# Dent_Sheet_ESP.net
KiCad netlist of a schematic drawn in Altium Designer
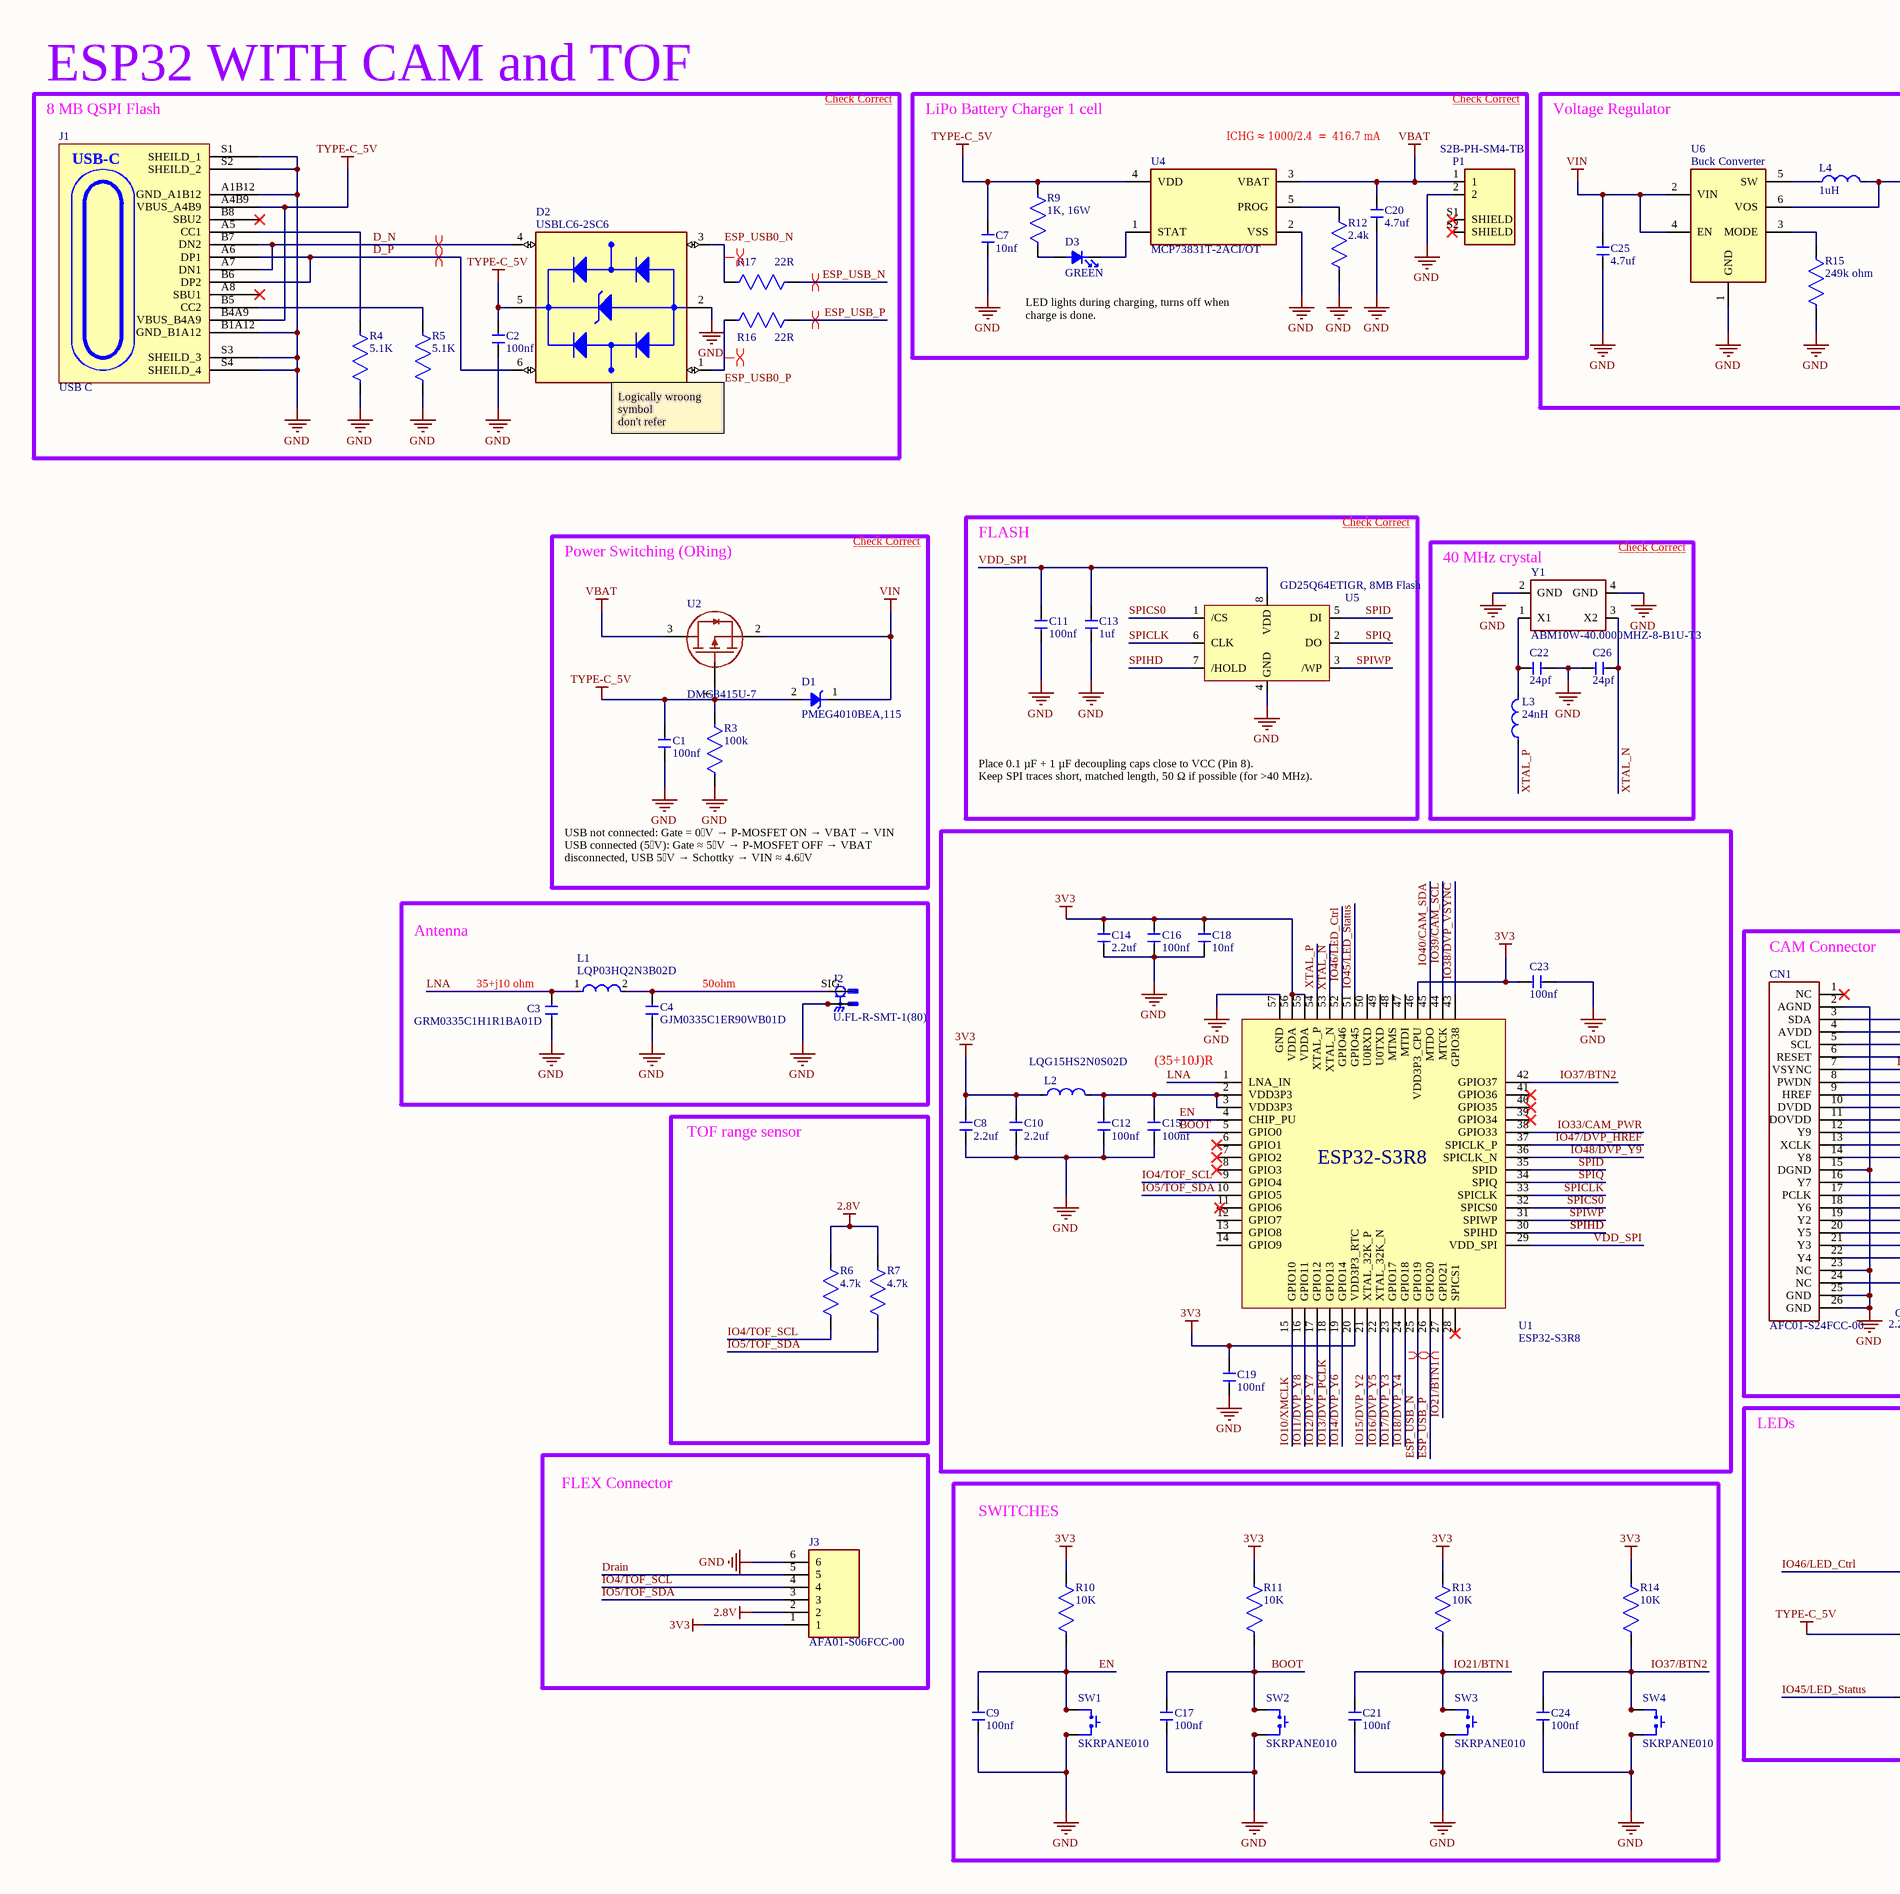
[diagram p0: Dent_Sheet_ESP.SchDoc, left]
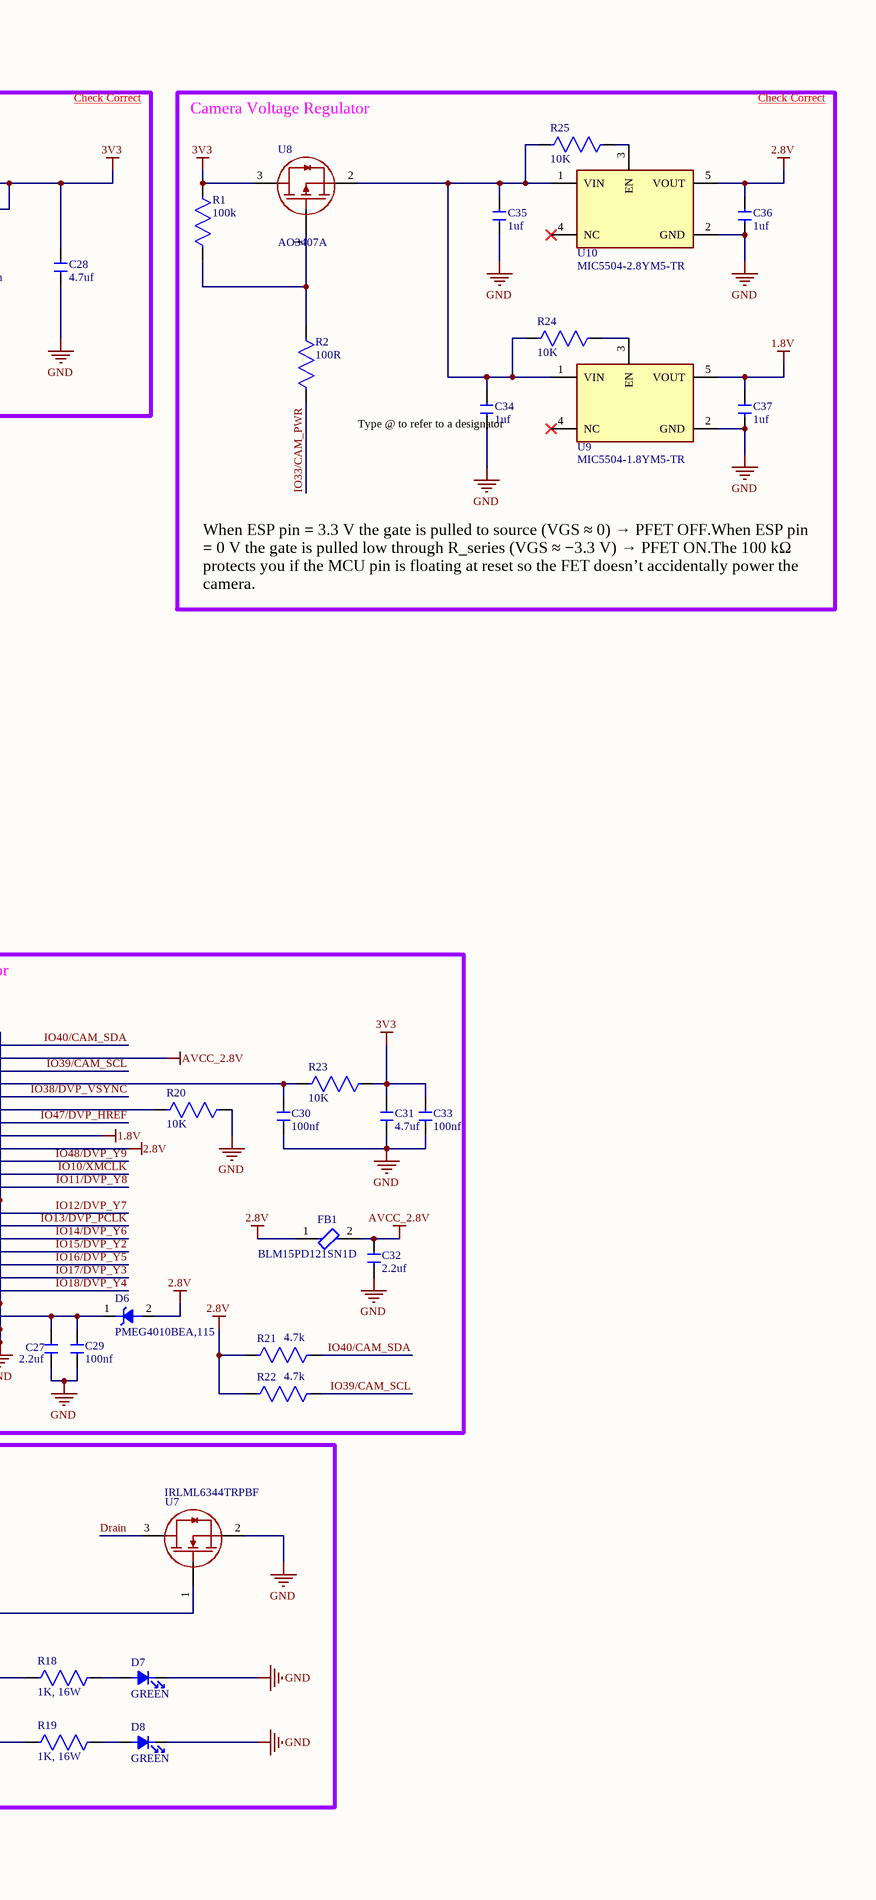
[diagram p1: Dent_Sheet_ESP.SchDoc, right]

(export (version "E")
  (design (tool "Eeschema 10.0.6"))
  (components
    (comp (ref "C1")
      (value "100nf")
      (footprint "CAPC1005X55N")
      (description "CAP CER 100NF 10V X7R 0402")
      (fields
        (field (name "MANUFACTURER") "Samsung")
        (field (name "MANUFACTURER PART NUMBER") "CL05B104KP5VPNC")
      )
      (libsource (lib "Dent_Schlib") (part "100nf"))
    )
    (comp (ref "C2")
      (value "100nf")
      (footprint "CAPC1005X55N")
      (description "CAP CER 100NF 10V X7R 0402")
      (fields
        (field (name "MANUFACTURER") "Samsung")
        (field (name "MANUFACTURER PART NUMBER") "CL05B104KP5VPNC")
      )
      (libsource (lib "Dent_Schlib") (part "100nf"))
    )
    (comp (ref "C3")
      (value "GRM0335C1H1R1BA01D")
      (footprint "FP-GRM033-0_03-MFG")
      (description "Chip Multilayer Ceramic Capacitors for General Purpose, 0201, 1.1pF, C0G, 30ppm/°C, 0.1pF, 50V")
      (fields (field (name "LCSC PART NO.") "C384969"))
      (libsource (lib "Dent_Schlib") (part "CMP-2010-01082-2"))
    )
    (comp (ref "C4")
      (value "GJM0335C1ER90WB01D")
      (footprint "FP-GJM033-0_03-MFG")
      (description "Ceramic Capacitor 0.9pF ±0.05pF 25V C0G 0201 (0603 Metric)")
      (fields (field (name "LCSC PART NO.") "C471401"))
      (libsource (lib "Dent_Schlib") (part "CMP-2010-00924-2"))
    )
    (comp (ref "C7")
      (value "10nf")
      (footprint "CAPC1005X55N")
      (description "CAP CER 10000PF 50V X7R 0402")
      (fields
        (field (name "MANUFACTURER") "Samsung")
        (field (name "MANUFACTURER PART NUMBER") "CL05B103KB5NNNC")
      )
      (libsource (lib "Dent_Schlib") (part "10nf"))
    )
    (comp (ref "C8")
      (value "2.2uf")
      (footprint "CAPC1005X55N")
      (description "CAP CER 2.2UF 10V X5R 0402")
      (fields
        (field (name "MANUFACTURER") "Samsung")
        (field (name "MANUFACTURER PART NUMBER") "CL05A225KP5NSNC")
      )
      (libsource (lib "Dent_Schlib") (part "2.2uf"))
    )
    (comp (ref "C9")
      (value "100nf")
      (footprint "CAPC1005X55N")
      (description "CAP CER 100NF 10V X7R 0402")
      (fields
        (field (name "MANUFACTURER") "Samsung")
        (field (name "MANUFACTURER PART NUMBER") "CL05B104KP5VPNC")
      )
      (libsource (lib "Dent_Schlib") (part "100nf"))
    )
    (comp (ref "C10")
      (value "2.2uf")
      (footprint "CAPC1005X55N")
      (description "CAP CER 2.2UF 10V X5R 0402")
      (fields
        (field (name "MANUFACTURER") "Samsung")
        (field (name "MANUFACTURER PART NUMBER") "CL05A225KP5NSNC")
      )
      (libsource (lib "Dent_Schlib") (part "2.2uf"))
    )
    (comp (ref "C11")
      (value "100nf")
      (footprint "CAPC1005X55N")
      (description "CAP CER 100NF 10V X7R 0402")
      (fields
        (field (name "MANUFACTURER") "Samsung")
        (field (name "MANUFACTURER PART NUMBER") "CL05B104KP5VPNC")
      )
      (libsource (lib "Dent_Schlib") (part "100nf"))
    )
    (comp (ref "C12")
      (value "100nf")
      (footprint "CAPC1005X55N")
      (description "CAP CER 100NF 10V X7R 0402")
      (fields
        (field (name "MANUFACTURER") "Samsung")
        (field (name "MANUFACTURER PART NUMBER") "CL05B104KP5VPNC")
      )
      (libsource (lib "Dent_Schlib") (part "100nf"))
    )
    (comp (ref "C13")
      (value "1uf")
      (footprint "CAPC1005X55N")
      (description "CAP CER 1UF 25V X5R 0402")
      (fields
        (field (name "MANUFACTURER") "Samsung")
        (field (name "MANUFACTURER PART NUMBER") "CL05A105KA5NQNC")
      )
      (libsource (lib "Dent_Schlib") (part "1uf"))
    )
    (comp (ref "C14")
      (value "2.2uf")
      (footprint "CAPC1005X55N")
      (description "CAP CER 2.2UF 10V X5R 0402")
      (fields
        (field (name "MANUFACTURER") "Samsung")
        (field (name "MANUFACTURER PART NUMBER") "CL05A225KP5NSNC")
      )
      (libsource (lib "Dent_Schlib") (part "2.2uf"))
    )
    (comp (ref "C15")
      (value "100nf")
      (footprint "CAPC1005X55N")
      (description "CAP CER 100NF 10V X7R 0402")
      (fields
        (field (name "MANUFACTURER") "Samsung")
        (field (name "MANUFACTURER PART NUMBER") "CL05B104KP5VPNC")
      )
      (libsource (lib "Dent_Schlib") (part "100nf"))
    )
    (comp (ref "C16")
      (value "100nf")
      (footprint "CAPC1005X55N")
      (description "CAP CER 100NF 10V X7R 0402")
      (fields
        (field (name "MANUFACTURER") "Samsung")
        (field (name "MANUFACTURER PART NUMBER") "CL05B104KP5VPNC")
      )
      (libsource (lib "Dent_Schlib") (part "100nf"))
    )
    (comp (ref "C17")
      (value "100nf")
      (footprint "CAPC1005X55N")
      (description "CAP CER 100NF 10V X7R 0402")
      (fields
        (field (name "MANUFACTURER") "Samsung")
        (field (name "MANUFACTURER PART NUMBER") "CL05B104KP5VPNC")
      )
      (libsource (lib "Dent_Schlib") (part "100nf"))
    )
    (comp (ref "C18")
      (value "10nf")
      (footprint "CAPC1005X55N")
      (description "CAP CER 10000PF 50V X7R 0402")
      (fields
        (field (name "MANUFACTURER") "Samsung")
        (field (name "MANUFACTURER PART NUMBER") "CL05B103KB5NNNC")
      )
      (libsource (lib "Dent_Schlib") (part "10nf"))
    )
    (comp (ref "C19")
      (value "100nf")
      (footprint "CAPC1005X55N")
      (description "CAP CER 100NF 10V X7R 0402")
      (fields
        (field (name "MANUFACTURER") "Samsung")
        (field (name "MANUFACTURER PART NUMBER") "CL05B104KP5VPNC")
      )
      (libsource (lib "Dent_Schlib") (part "100nf"))
    )
    (comp (ref "C20")
      (value "4.7uf")
      (footprint "CAPC1005X55N")
      (description "CAP CER 4.7UF 10V X5R 0402")
      (fields
        (field (name "MANUFACTURER") "Samsung")
        (field (name "MANUFACTURER PART NUMBER") "CL05A475KP5ZRNC")
      )
      (libsource (lib "Dent_Schlib") (part "4.7uf"))
    )
    (comp (ref "C21")
      (value "100nf")
      (footprint "CAPC1005X55N")
      (description "CAP CER 100NF 10V X7R 0402")
      (fields
        (field (name "MANUFACTURER") "Samsung")
        (field (name "MANUFACTURER PART NUMBER") "CL05B104KP5VPNC")
      )
      (libsource (lib "Dent_Schlib") (part "100nf"))
    )
    (comp (ref "C22")
      (value "24pf")
      (footprint "CAPC1005X55N")
      (description "CAP CER 24PF 50V C0G/NPO 0402")
      (fields
        (field (name "MANUFACTURER") "Yageo")
        (field (name "MANUFACTURER PART NUMBER") "CC0402GRNPO9BN240")
      )
      (libsource (lib "Dent_Schlib") (part "24pf"))
    )
    (comp (ref "C23")
      (value "100nf")
      (footprint "CAPC1005X55N")
      (description "CAP CER 100NF 10V X7R 0402")
      (fields
        (field (name "MANUFACTURER") "Samsung")
        (field (name "MANUFACTURER PART NUMBER") "CL05B104KP5VPNC")
      )
      (libsource (lib "Dent_Schlib") (part "100nf"))
    )
    (comp (ref "C24")
      (value "100nf")
      (footprint "CAPC1005X55N")
      (description "CAP CER 100NF 10V X7R 0402")
      (fields
        (field (name "MANUFACTURER") "Samsung")
        (field (name "MANUFACTURER PART NUMBER") "CL05B104KP5VPNC")
      )
      (libsource (lib "Dent_Schlib") (part "100nf"))
    )
    (comp (ref "C25")
      (value "4.7uf")
      (footprint "CAPC1005X55N")
      (description "CAP CER 4.7UF 10V X5R 0402")
      (fields
        (field (name "MANUFACTURER") "Samsung")
        (field (name "MANUFACTURER PART NUMBER") "CL05A475KP5ZRNC")
      )
      (libsource (lib "Dent_Schlib") (part "4.7uf"))
    )
    (comp (ref "C26")
      (value "24pf")
      (footprint "CAPC1005X55N")
      (description "CAP CER 24PF 50V C0G/NPO 0402")
      (fields
        (field (name "MANUFACTURER") "Yageo")
        (field (name "MANUFACTURER PART NUMBER") "CC0402GRNPO9BN240")
      )
      (libsource (lib "Dent_Schlib") (part "24pf"))
    )
    (comp (ref "C27")
      (value "2.2uf")
      (footprint "CAPC1005X55N")
      (description "CAP CER 2.2UF 10V X5R 0402")
      (fields
        (field (name "MANUFACTURER") "Samsung")
        (field (name "MANUFACTURER PART NUMBER") "CL05A225KP5NSNC")
      )
      (libsource (lib "Dent_Schlib") (part "2.2uf"))
    )
    (comp (ref "C28")
      (value "4.7uf")
      (footprint "CAPC1005X55N")
      (description "CAP CER 4.7UF 10V X5R 0402")
      (fields
        (field (name "MANUFACTURER") "Samsung")
        (field (name "MANUFACTURER PART NUMBER") "CL05A475KP5ZRNC")
      )
      (libsource (lib "Dent_Schlib") (part "4.7uf"))
    )
    (comp (ref "C29")
      (value "100nf")
      (footprint "CAPC1005X55N")
      (description "CAP CER 100NF 10V X7R 0402")
      (fields
        (field (name "MANUFACTURER") "Samsung")
        (field (name "MANUFACTURER PART NUMBER") "CL05B104KP5VPNC")
      )
      (libsource (lib "Dent_Schlib") (part "100nf"))
    )
    (comp (ref "C30")
      (value "100nf")
      (footprint "CAPC1005X55N")
      (description "CAP CER 100NF 10V X7R 0402")
      (fields
        (field (name "MANUFACTURER") "Samsung")
        (field (name "MANUFACTURER PART NUMBER") "CL05B104KP5VPNC")
      )
      (libsource (lib "Dent_Schlib") (part "100nf"))
    )
    (comp (ref "C31")
      (value "4.7uf")
      (footprint "CAPC1005X55N")
      (description "CAP CER 4.7UF 10V X5R 0402")
      (fields
        (field (name "MANUFACTURER") "Samsung")
        (field (name "MANUFACTURER PART NUMBER") "CL05A475KP5ZRNC")
      )
      (libsource (lib "Dent_Schlib") (part "4.7uf"))
    )
    (comp (ref "C32")
      (value "2.2uf")
      (footprint "CAPC1005X55N")
      (description "CAP CER 2.2UF 10V X5R 0402")
      (fields
        (field (name "MANUFACTURER") "Samsung")
        (field (name "MANUFACTURER PART NUMBER") "CL05A225KP5NSNC")
      )
      (libsource (lib "Dent_Schlib") (part "2.2uf"))
    )
    (comp (ref "C33")
      (value "100nf")
      (footprint "CAPC1005X55N")
      (description "CAP CER 100NF 10V X7R 0402")
      (fields
        (field (name "MANUFACTURER") "Samsung")
        (field (name "MANUFACTURER PART NUMBER") "CL05B104KP5VPNC")
      )
      (libsource (lib "Dent_Schlib") (part "100nf"))
    )
    (comp (ref "C34")
      (value "1uf")
      (footprint "CAPC1005X55N")
      (description "CAP CER 1UF 25V X5R 0402")
      (fields
        (field (name "MANUFACTURER") "Samsung")
        (field (name "MANUFACTURER PART NUMBER") "CL05A105KA5NQNC")
      )
      (libsource (lib "Dent_Schlib") (part "1uf"))
    )
    (comp (ref "C35")
      (value "1uf")
      (footprint "CAPC1005X55N")
      (description "CAP CER 1UF 25V X5R 0402")
      (fields
        (field (name "MANUFACTURER") "Samsung")
        (field (name "MANUFACTURER PART NUMBER") "CL05A105KA5NQNC")
      )
      (libsource (lib "Dent_Schlib") (part "1uf"))
    )
    (comp (ref "C36")
      (value "1uf")
      (footprint "CAPC1005X55N")
      (description "CAP CER 1UF 25V X5R 0402")
      (fields
        (field (name "MANUFACTURER") "Samsung")
        (field (name "MANUFACTURER PART NUMBER") "CL05A105KA5NQNC")
      )
      (libsource (lib "Dent_Schlib") (part "1uf"))
    )
    (comp (ref "C37")
      (value "1uf")
      (footprint "CAPC1005X55N")
      (description "CAP CER 1UF 25V X5R 0402")
      (fields
        (field (name "MANUFACTURER") "Samsung")
        (field (name "MANUFACTURER PART NUMBER") "CL05A105KA5NQNC")
      )
      (libsource (lib "Dent_Schlib") (part "1uf"))
    )
    (comp (ref "CN1")
      (value "AFC01-S24FCC-00")
      (footprint "FH52-24S-0.5SH")
      (description "SMD,P=0.5mm,Surface Mount,Right Angle")
      (fields (field (name "MANUFACTURER") "Hirose") (field (name "LCSC PART NO.") "C262276"))
      (libsource (lib "Dent_Schlib") (part "AFC01-S24FCC-00"))
    )
    (comp (ref "D1")
      (value "PMEG4010BEA,115")
      (footprint "SOD2512X110N")
      (description "DIODE SCHOTTKY 40V 1A SOD323")
      (fields (field (name "MANUFACTURER") "Nexperia") (field (name "LCSC PART NO.") "C36975"))
      (libsource (lib "Dent_Schlib") (part "PMEG4010BEA,115"))
    )
    (comp (ref "D2")
      (value "USBLC6-2SC6")
      (footprint "SOT95P280X145-6N")
      (description "17V Clamp 5A (8/20µs) Ipp Tvs Diode Surface Mount SOT-23-6")
      (fields (field (name "MANUFACTURER") "STMicroelectronics") (field (name "LCSC PART NO.") "C7519"))
      (libsource (lib "Dent_Schlib") (part "USBLC6-2SC6"))
    )
    (comp (ref "D3")
      (value "GREEN")
      (footprint "LEDC1005X35N")
      (description "LED YLW-GRN 0402 SMD")
      (fields
        (field (name "MANUFACTURER") "Vishay")
        (field (name "MANUFACTURER PART NUMBER") "VLMG1500-GS08")
      )
      (libsource (lib "Dent_Schlib") (part "VLMG1500-GS08"))
    )
    (comp (ref "D6")
      (value "PMEG4010BEA,115")
      (footprint "SOD2512X110N")
      (description "DIODE SCHOTTKY 40V 1A SOD323")
      (fields (field (name "MANUFACTURER") "Nexperia") (field (name "LCSC PART NO.") "C36975"))
      (libsource (lib "Dent_Schlib") (part "PMEG4010BEA,115"))
    )
    (comp (ref "D7")
      (value "GREEN")
      (footprint "LEDC1005X35N")
      (description "LED YLW-GRN 0402 SMD")
      (fields
        (field (name "MANUFACTURER") "Vishay")
        (field (name "MANUFACTURER PART NUMBER") "VLMG1500-GS08")
      )
      (libsource (lib "Dent_Schlib") (part "VLMG1500-GS08"))
    )
    (comp (ref "D8")
      (value "GREEN")
      (footprint "LEDC1005X35N")
      (description "LED YLW-GRN 0402 SMD")
      (fields
        (field (name "MANUFACTURER") "Vishay")
        (field (name "MANUFACTURER PART NUMBER") "VLMG1500-GS08")
      )
      (libsource (lib "Dent_Schlib") (part "VLMG1500-GS08"))
    )
    (comp (ref "FB1")
      (value "BLM15PD121SN1D")
      (footprint "FP-BLM15-0_05-IPC_B")
      (description "Chip Ferrite Bead, 0402, 120Ω @ 100MHz, 0.09Ω, 25%, 1.3A")
      (fields (field (name "TOLERANCE") "25%") (field (name "LCSC PART NO.") "C76891"))
      (libsource (lib "Dent_Schlib") (part "BLM15PD121SN1D"))
    )
    (comp (ref "J1")
      (value "USB C")
      (footprint "FP-2171790001-MFG")
      (description "USB Connector, USB Type C, USB 2.0, Receptacle, 16 Ways, Surface Mount, Through Hole Mount")
      (fields (field (name "MANUFACTURER") "Molex") (field (name "MANUFACTURER PART NUMBER") "217179-0001"))
      (libsource (lib "Dent_Schlib") (part "217179-0001"))
    )
    (comp (ref "J2")
      (value "U.FL-R-SMT-1(80)")
      (footprint "HIROSE_U.FL-R-SMT-1(80)")
      (description "U.FL (UMCC) Connector Receptacle, Male Pin 50 Ohms Surface Mount Solder")
      (fields (field (name "LCSC PART NO.") "C88374"))
      (libsource (lib "Dent_Schlib") (part "U.FL-R-SMT-1(80)"))
    )
    (comp (ref "J3")
      (value "AFA01-S06FCC-00")
      (footprint "JUSHUO_AFA01-S06FCC-00")
      (description "Pitch 1.00mm FPC Connector SMT Type")
      (fields (field (name "MF") "Shenzhen Jushuo Electronics Co") (field (name "LCSC PART NO.") "C262262"))
      (libsource (lib "Dent_Schlib") (part "AFA01-S06FCC-00"))
    )
    (comp (ref "L1")
      (value "LQP03HQ2N3B02D")
      (footprint "FP-LQP02HV_02-MFG")
      (description "Film type RF Inductor 2.3nH ±0.1nH 600mA 0.12Ω 0201 (0603)")
      (fields (field (name "LCSC PART NO.") "C2975186"))
      (libsource (lib "Dent_Schlib") (part "CMP-06042-004543-1"))
    )
    (comp (ref "L2")
      (value "LQG15HS2N0S02D")
      (footprint "INDC1005X55N")
      (description "Inductor RF Chip Multi-Layer 2nH 0.3nH 100MHz 8Q-Factor Air 300mA 100mOhm DCR 0402 Paper T/R")
      (fields (field (name "MANUFACTURER") "Murata") (field (name "TOLERANCE") "15%"))
      (libsource (lib "Dent_Schlib") (part "LQG15HS2N0S02D"))
    )
    (comp (ref "L3")
      (value "24nH")
      (footprint "INDC1005X60N")
      (description "FIXED IND 24NH 280MA 0.52OHM SMD")
      (fields
        (field (name "MANUFACTURER") "Murata")
        (field (name "MANUFACTURER PART NUMBER") "LQW15AN24NJ00D")
      )
      (libsource (lib "Dent_Schlib") (part "24nH"))
    )
    (comp (ref "L4")
      (value "1uH")
      (footprint "INDC2016X100N")
      (description "1 µH Shielded Drum Core, Wirewound Inductor 3.1 A 70mOhm Max 0806 (2016 Metric)")
      (fields
        (field (name "MANUFACTURER") "Murata")
        (field (name "MANUFACTURER PART NUMBER") "DFE201610P-1R0M=P2")
      )
      (libsource (lib "Dent_Schlib") (part "1uH"))
    )
    (comp (ref "P1")
      (value "S2B-PH-SM4-TB")
      (footprint "JST_S2B-PH-SM4-TB(LF)(SN)")
      (description "Header S2B-PH-SM4-TB, 2.00mm, 2-contacts, side entry, SMT, /1000/reel")
      (fields (field (name "MANUFACTURER") "JST") (field (name "LCSC PART NO.") "C295747"))
      (libsource (lib "Dent_Schlib") (part "S2B-PH-SM4-TB"))
    )
    (comp (ref "R1")
      (value "100k")
      (footprint "RESC1005X40N")
      (description "RES 100K OHM 1% 1/16W 0402")
      (fields
        (field (name "MANUFACTURER") "Yageo")
        (field (name "MANUFACTURER PART NUMBER") "RC0402FR-07100KL")
      )
      (libsource (lib "Dent_Schlib") (part "100k"))
    )
    (comp (ref "R2")
      (value "100R")
      (footprint "RESC1005X40N")
      (fields
        (field (name "MANUFACTURER") "Yageo")
        (field (name "MANUFACTURER PART NUMBER") "RC0402JR-07100KL")
        (field (name "TOLERANCE") "5%")
      )
      (libsource (lib "Dent_Schlib") (part "100R"))
    )
    (comp (ref "R3")
      (value "100k")
      (footprint "RESC1005X40N")
      (description "RES 100K OHM 1% 1/16W 0402")
      (fields
        (field (name "MANUFACTURER") "Yageo")
        (field (name "MANUFACTURER PART NUMBER") "RC0402FR-07100KL")
      )
      (libsource (lib "Dent_Schlib") (part "100k"))
    )
    (comp (ref "R4")
      (value "5.1K")
      (footprint "RESC1005X40N")
      (fields
        (field (name "MANUFACTURER") "Yageo")
        (field (name "MANUFACTURER PART NUMBER") "RC0402FR-075K1L")
        (field (name "TOLERANCE") "1%")
      )
      (libsource (lib "Dent_Schlib") (part "5.1K"))
    )
    (comp (ref "R5")
      (value "5.1K")
      (footprint "RESC1005X40N")
      (fields
        (field (name "MANUFACTURER") "Yageo")
        (field (name "MANUFACTURER PART NUMBER") "RC0402FR-075K1L")
        (field (name "TOLERANCE") "1%")
      )
      (libsource (lib "Dent_Schlib") (part "5.1K"))
    )
    (comp (ref "R6")
      (value "4.7k")
      (footprint "RESC1005X40N")
      (description "RES 4.7K OHM 1% 1/16W 0402")
      (fields
        (field (name "MANUFACTURER") "Yageo")
        (field (name "MANUFACTURER PART NUMBER") "RC0402FR-074K7L")
      )
      (libsource (lib "Dent_Schlib") (part "4.7k"))
    )
    (comp (ref "R7")
      (value "4.7k")
      (footprint "RESC1005X40N")
      (description "RES 4.7K OHM 1% 1/16W 0402")
      (fields
        (field (name "MANUFACTURER") "Yageo")
        (field (name "MANUFACTURER PART NUMBER") "RC0402FR-074K7L")
      )
      (libsource (lib "Dent_Schlib") (part "4.7k"))
    )
    (comp (ref "R9")
      (value "1K, 16W")
      (footprint "RESC1005X40N")
      (description "RES 1K OHM 1% 1/16W 0402")
      (fields
        (field (name "MANUFACTURER") "Yageo")
        (field (name "MANUFACTURER PART NUMBER") "RC0402FR-071KL")
      )
      (libsource (lib "Dent_Schlib") (part "1K, 16W"))
    )
    (comp (ref "R10")
      (value "10K")
      (footprint "RESC1005X40N")
      (description "Res Thick Film 0402 10K Ohm 5% 0.125W(1/8W) ±200ppm/C Pad SMD T/R")
      (fields
        (field (name "MANUFACTURER") "Yageo Group")
        (field (name "MANUFACTURER PART NUMBER") "RC0402JR-7W10KL")
      )
      (libsource (lib "Dent_Schlib") (part "10K"))
    )
    (comp (ref "R11")
      (value "10K")
      (footprint "RESC1005X40N")
      (description "Res Thick Film 0402 10K Ohm 5% 0.125W(1/8W) ±200ppm/C Pad SMD T/R")
      (fields
        (field (name "MANUFACTURER") "Yageo Group")
        (field (name "MANUFACTURER PART NUMBER") "RC0402JR-7W10KL")
      )
      (libsource (lib "Dent_Schlib") (part "10K"))
    )
    (comp (ref "R12")
      (value "2.4k")
      (footprint "RESC1005X40N")
      (description "RES SMD 2.4K OHM 1% 1/16W 0402")
      (fields
        (field (name "MANUFACTURER") "Samsung")
        (field (name "MANUFACTURER PART NUMBER") "RC1005F242CS")
      )
      (libsource (lib "Dent_Schlib") (part "2.4k"))
    )
    (comp (ref "R13")
      (value "10K")
      (footprint "RESC1005X40N")
      (description "Res Thick Film 0402 10K Ohm 5% 0.125W(1/8W) ±200ppm/C Pad SMD T/R")
      (fields
        (field (name "MANUFACTURER") "Yageo Group")
        (field (name "MANUFACTURER PART NUMBER") "RC0402JR-7W10KL")
      )
      (libsource (lib "Dent_Schlib") (part "10K"))
    )
    (comp (ref "R14")
      (value "10K")
      (footprint "RESC1005X40N")
      (description "Res Thick Film 0402 10K Ohm 5% 0.125W(1/8W) ±200ppm/C Pad SMD T/R")
      (fields
        (field (name "MANUFACTURER") "Yageo Group")
        (field (name "MANUFACTURER PART NUMBER") "RC0402JR-7W10KL")
      )
      (libsource (lib "Dent_Schlib") (part "10K"))
    )
    (comp (ref "R15")
      (value "249k ohm")
      (footprint "RESC1005X40N")
      (description "249 kOhms ±1% 0.063W, 1/16W Chip Resistor 0402 (1005 Metric) Moisture Resistant Thick Film")
      (fields
        (field (name "MANUFACTURER") "Yageo")
        (field (name "MANUFACTURER PART NUMBER") "RC0402FR-07249KL")
      )
      (libsource (lib "Dent_Schlib") (part "249k ohm"))
    )
    (comp (ref "R16")
      (value "22R")
      (footprint "RESC1005X40N")
      (description "RES 22 OHM 5% 1/8W 0402")
      (fields
        (field (name "MANUFACTURER") "Yageo Group")
        (field (name "MANUFACTURER PART NUMBER") "AC0402JR-7W22RL")
      )
      (libsource (lib "Dent_Schlib") (part "22R"))
    )
    (comp (ref "R17")
      (value "22R")
      (footprint "RESC1005X40N")
      (description "RES 22 OHM 5% 1/8W 0402")
      (fields
        (field (name "MANUFACTURER") "Yageo Group")
        (field (name "MANUFACTURER PART NUMBER") "AC0402JR-7W22RL")
      )
      (libsource (lib "Dent_Schlib") (part "22R"))
    )
    (comp (ref "R18")
      (value "1K, 16W")
      (footprint "RESC1005X40N")
      (description "RES 1K OHM 1% 1/16W 0402")
      (fields
        (field (name "MANUFACTURER") "Yageo")
        (field (name "MANUFACTURER PART NUMBER") "RC0402FR-071KL")
      )
      (libsource (lib "Dent_Schlib") (part "1K, 16W"))
    )
    (comp (ref "R19")
      (value "1K, 16W")
      (footprint "RESC1005X40N")
      (description "RES 1K OHM 1% 1/16W 0402")
      (fields
        (field (name "MANUFACTURER") "Yageo")
        (field (name "MANUFACTURER PART NUMBER") "RC0402FR-071KL")
      )
      (libsource (lib "Dent_Schlib") (part "1K, 16W"))
    )
    (comp (ref "R20")
      (value "10K")
      (footprint "RESC1005X40N")
      (description "Res Thick Film 0402 10K Ohm 5% 0.125W(1/8W) ±200ppm/C Pad SMD T/R")
      (fields
        (field (name "MANUFACTURER") "Yageo Group")
        (field (name "MANUFACTURER PART NUMBER") "RC0402JR-7W10KL")
      )
      (libsource (lib "Dent_Schlib") (part "10K"))
    )
    (comp (ref "R21")
      (value "4.7k")
      (footprint "RESC1005X40N")
      (description "RES 4.7K OHM 1% 1/16W 0402")
      (fields
        (field (name "MANUFACTURER") "Yageo")
        (field (name "MANUFACTURER PART NUMBER") "RC0402FR-074K7L")
      )
      (libsource (lib "Dent_Schlib") (part "4.7k"))
    )
    (comp (ref "R22")
      (value "4.7k")
      (footprint "RESC1005X40N")
      (description "RES 4.7K OHM 1% 1/16W 0402")
      (fields
        (field (name "MANUFACTURER") "Yageo")
        (field (name "MANUFACTURER PART NUMBER") "RC0402FR-074K7L")
      )
      (libsource (lib "Dent_Schlib") (part "4.7k"))
    )
    (comp (ref "R23")
      (value "10K")
      (footprint "RESC1005X40N")
      (description "Res Thick Film 0402 10K Ohm 5% 0.125W(1/8W) ±200ppm/C Pad SMD T/R")
      (fields
        (field (name "MANUFACTURER") "Yageo Group")
        (field (name "MANUFACTURER PART NUMBER") "RC0402JR-7W10KL")
      )
      (libsource (lib "Dent_Schlib") (part "10K"))
    )
    (comp (ref "R24")
      (value "10K")
      (footprint "RESC1005X40N")
      (description "Res Thick Film 0402 10K Ohm 5% 0.125W(1/8W) ±200ppm/C Pad SMD T/R")
      (fields
        (field (name "MANUFACTURER") "Yageo Group")
        (field (name "MANUFACTURER PART NUMBER") "RC0402JR-7W10KL")
      )
      (libsource (lib "Dent_Schlib") (part "10K"))
    )
    (comp (ref "R25")
      (value "10K")
      (footprint "RESC1005X40N")
      (description "Res Thick Film 0402 10K Ohm 5% 0.125W(1/8W) ±200ppm/C Pad SMD T/R")
      (fields
        (field (name "MANUFACTURER") "Yageo Group")
        (field (name "MANUFACTURER PART NUMBER") "RC0402JR-7W10KL")
      )
      (libsource (lib "Dent_Schlib") (part "10K"))
    )
    (comp (ref "SW1")
      (value "SKRPANE010")
      (footprint "SKRPANE010")
      (description "Tactile Switch SPST-NO Top Actuated Surface Mount")
      (fields (field (name "MANUFACTURER") "ALPS") (field (name "LCSC PART NO.") "C470426"))
      (libsource (lib "Dent_Schlib") (part "SKRPANE010"))
    )
    (comp (ref "SW2")
      (value "SKRPANE010")
      (footprint "SKRPANE010")
      (description "Tactile Switch SPST-NO Top Actuated Surface Mount")
      (fields (field (name "MANUFACTURER") "ALPS") (field (name "LCSC PART NO.") "C470426"))
      (libsource (lib "Dent_Schlib") (part "SKRPANE010"))
    )
    (comp (ref "SW3")
      (value "SKRPANE010")
      (footprint "SKRPANE010")
      (description "Tactile Switch SPST-NO Top Actuated Surface Mount")
      (fields (field (name "MANUFACTURER") "ALPS") (field (name "LCSC PART NO.") "C470426"))
      (libsource (lib "Dent_Schlib") (part "SKRPANE010"))
    )
    (comp (ref "SW4")
      (value "SKRPANE010")
      (footprint "SKRPANE010")
      (description "Tactile Switch SPST-NO Top Actuated Surface Mount")
      (fields (field (name "MANUFACTURER") "ALPS") (field (name "LCSC PART NO.") "C470426"))
      (libsource (lib "Dent_Schlib") (part "SKRPANE010"))
    )
    (comp (ref "U1")
      (value "ESP32-S3R8")
      (footprint "FP-ESP32-S3R8-IPC_B")
      (description "IC RF TXRX+MCU BLE 56QFN")
      (fields (field (name "MANUFACTURER") "Espressif Systems") (field (name "LCSC PART NO.") "C2913194"))
      (libsource (lib "Dent_Schlib") (part "ESP32-S3R8"))
    )
    (comp (ref "U2")
      (value "DMG3415U-7")
      (footprint "SOT95P240X105-3N")
      (description "P-Channel 20 V 4A (Ta) 900mW (Ta) Surface Mount SOT-23-3")
      (fields (field (name "MANUFACTURER") "Diodes") (field (name "LCSC PART NO.") "C96616"))
      (libsource (lib "Dent_Schlib") (part "DMG3415U-7"))
    )
    (comp (ref "U4")
      (value "MCP73831T-2ACI/OT")
      (footprint "FP-C04-091-OT-IPC_A")
      (description "IC BATT CNTL LI-ION 1CEL SOT23-5")
      (fields (field (name "MANUFACTURER") "Microchip") (field (name "LCSC PART NO.") "C42432883"))
      (libsource (lib "Dent_Schlib") (part "MCP73831T-2ACI/OT"))
    )
    (comp (ref "U5")
      (value "GD25Q64ETIGR, 8MB Flash")
      (footprint "SOIC127P600X175-8N")
      (description "2.7V~3.6V -40℃~85℃ 64MBIT 133MHZ SOP-8-150MIL Nor Flash Rohs")
      (fields
        (field (name "MANUFACTURER") "GigaDevice")
        (field (name "MANUFACTURER PART NUMBER") "GD25Q64ETIGR")
      )
      (libsource (lib "Dent_Schlib") (part "GD25Q64ETIGR"))
    )
    (comp (ref "U6")
      (value "Buck Converter")
      (footprint "SOT-563")
      (description "Buck Switching Regulator IC Positive Programmable 1.8V 1 Output 600mA SOT-563, SOT-666")
      (fields
        (field (name "MANUFACTURER") "Texas Instruments")
        (field (name "MANUFACTURER PART NUMBER") "TPS628438DRLR")
      )
      (libsource (lib "Dent_Schlib") (part "TPS628438DRLR"))
    )
    (comp (ref "U7")
      (value "IRLML6344TRPBF")
      (footprint "TRANS_IRLML6344TRPBF")
      (description "MOSFET N-CH 30V 5A MICRO3/SOT23")
      (fields (field (name "MANUFACTURER") "Infineon") (field (name "LCSC PART NO.") "C53550"))
      (libsource (lib "Dent_Schlib") (part "IRLML6344TRPBF"))
    )
    (comp (ref "U8")
      (value "AO3407A")
      (footprint "SOT-23-3L_AOS")
      (description "30V 4.3A 48mΩ@10V 2.5V@250uA 1 P-Channel SOT-23 MOSFETs ROHS")
      (fields
        (field (name "MANUFACTURER") "Alpha & Omega Semiconductor")
        (field (name "LCSC PART NO.") "C15155")
      )
      (libsource (lib "Dent_Schlib") (part "AO3407A"))
    )
    (comp (ref "U9")
      (value "MIC5504-1.8YM5-TR")
      (footprint "FP-SOT23-5LD-PL-1-IPC_C")
      (description "IC REG LINEAR 1.8V 300MA SOT23-5")
      (fields
        (field (name "OCTOPART") "https://octopart.com/mic5504-1.8ym5-tr-microchip-66803399")
        (field (name "MANUFACTURER") "Microchip")
      )
      (libsource (lib "Dent_Schlib") (part "MIC5504-1.8YM5-TR"))
    )
    (comp (ref "U10")
      (value "MIC5504-2.8YM5-TR")
      (footprint "FP-SOT23-5LD-PL-1-IPC_C")
      (description "IC REG LINEAR 2.8V 300MA SOT23-5")
      (fields (field (name "LCSC PART NO.") "C95749"))
      (libsource (lib "Dent_Schlib") (part "MIC5504-2.8YM5-TR"))
    )
    (comp (ref "Y1")
      (value "ABM10W-40.0000MHZ-8-B1U-T3")
      (footprint "XTAL_ABM10W-40.0000MHZ-8-B1U-T3")
      (description "Crystal, Quartz, 40 MHz, SMD, 2.5mm x 2mm x 0.6mm, 10 ppm, 8 pF, 10 ppm, ABM10W")
      (fields (field (name "MANUFACTURER") "Abracon") (field (name "TOLERANCE") "0.001%"))
      (libsource (lib "Dent_Schlib") (part "ABM10W-40.0000MHZ-8-B1U-T3"))
    )
  )
  (nets
    (net (code "1") (name "/BOOT") (class "Default")
      (node (ref "C17") (pin "2") (pinfunction "2_2") (pintype "passive"))
      (node (ref "R11") (pin "1") (pinfunction "1_1") (pintype "passive"))
      (node (ref "SW2") (pin "3") (pinfunction "3_3") (pintype "passive"))
      (node (ref "SW2") (pin "4") (pinfunction "4_4") (pintype "passive"))
      (node (ref "U1") (pin "5") (pinfunction "GPIO0_5") (pintype "passive"))
    )
    (net (code "2") (name "/D_N") (class "Default")
      (node (ref "D2") (pin "4") (pinfunction "I/O2_OUT_4") (pintype "bidirectional"))
      (node (ref "J1") (pin "A7") (pinfunction "DN1_A7") (pintype "passive"))
      (node (ref "J1") (pin "B7") (pinfunction "DN2_B7") (pintype "passive"))
    )
    (net (code "3") (name "/D_P") (class "Default")
      (node (ref "D2") (pin "6") (pinfunction "I/O1_OUT_6") (pintype "bidirectional"))
      (node (ref "J1") (pin "A6") (pinfunction "DP1_A6") (pintype "passive"))
      (node (ref "J1") (pin "B6") (pinfunction "DP2_B6") (pintype "passive"))
    )
    (net (code "4") (name "/Drain") (class "Default")
      (node (ref "J3") (pin "5") (pinfunction "5_5") (pintype "passive"))
      (node (ref "U7") (pin "3") (pinfunction "3_3") (pintype "passive"))
    )
    (net (code "5") (name "/EN") (class "Default")
      (node (ref "C9") (pin "2") (pinfunction "2_2") (pintype "passive"))
      (node (ref "R10") (pin "1") (pinfunction "1_1") (pintype "passive"))
      (node (ref "SW1") (pin "3") (pinfunction "3_3") (pintype "passive"))
      (node (ref "SW1") (pin "4") (pinfunction "4_4") (pintype "passive"))
      (node (ref "U1") (pin "4") (pinfunction "CHIP_PU_4") (pintype "passive"))
    )
    (net (code "6") (name "/ESP_USB0_N") (class "Default")
      (node (ref "D2") (pin "3") (pinfunction "I/O2_IN_3") (pintype "bidirectional"))
      (node (ref "R17") (pin "1") (pinfunction "1_1") (pintype "passive"))
    )
    (net (code "7") (name "/ESP_USB0_P") (class "Default")
      (node (ref "D2") (pin "1") (pinfunction "I/O1_IN_1") (pintype "bidirectional"))
      (node (ref "R16") (pin "1") (pinfunction "1_1") (pintype "passive"))
    )
    (net (code "8") (name "/ESP_USB_N") (class "Default")
      (node (ref "R17") (pin "2") (pinfunction "2_2") (pintype "passive"))
      (node (ref "U1") (pin "25") (pinfunction "GPIO19_25") (pintype "passive"))
    )
    (net (code "9") (name "/ESP_USB_P") (class "Default")
      (node (ref "R16") (pin "2") (pinfunction "2_2") (pintype "passive"))
      (node (ref "U1") (pin "26") (pinfunction "GPIO20_26") (pintype "passive"))
    )
    (net (code "10") (name "/IO4{slash}TOF_SCL") (class "Default")
      (node (ref "J3") (pin "4") (pinfunction "4_4") (pintype "passive"))
      (node (ref "R6") (pin "1") (pinfunction "1_1") (pintype "passive"))
      (node (ref "U1") (pin "9") (pinfunction "GPIO4_9") (pintype "passive"))
    )
    (net (code "11") (name "/IO5{slash}TOF_SDA") (class "Default")
      (node (ref "J3") (pin "3") (pinfunction "3_3") (pintype "passive"))
      (node (ref "R7") (pin "1") (pinfunction "1_1") (pintype "passive"))
      (node (ref "U1") (pin "10") (pinfunction "GPIO5_10") (pintype "passive"))
    )
    (net (code "12") (name "/IO10{slash}XMCLK") (class "Default")
      (node (ref "CN1") (pin "13") (pinfunction "XCLK_13") (pintype "passive"))
      (node (ref "U1") (pin "15") (pinfunction "GPIO10_15") (pintype "passive"))
    )
    (net (code "13") (name "/IO11{slash}DVP_Y8") (class "Default")
      (node (ref "CN1") (pin "14") (pinfunction "Y8_14") (pintype "passive"))
      (node (ref "U1") (pin "16") (pinfunction "GPIO11_16") (pintype "passive"))
    )
    (net (code "14") (name "/IO12{slash}DVP_Y7") (class "Default")
      (node (ref "CN1") (pin "16") (pinfunction "Y7_16") (pintype "passive"))
      (node (ref "U1") (pin "17") (pinfunction "GPIO12_17") (pintype "passive"))
    )
    (net (code "15") (name "/IO13{slash}DVP_PCLK") (class "Default")
      (node (ref "CN1") (pin "17") (pinfunction "PCLK_17") (pintype "passive"))
      (node (ref "U1") (pin "18") (pinfunction "GPIO13_18") (pintype "passive"))
    )
    (net (code "16") (name "/IO14{slash}DVP_Y6") (class "Default")
      (node (ref "CN1") (pin "18") (pinfunction "Y6_18") (pintype "passive"))
      (node (ref "U1") (pin "19") (pinfunction "GPIO14_19") (pintype "passive"))
    )
    (net (code "17") (name "/IO15{slash}DVP_Y2") (class "Default")
      (node (ref "CN1") (pin "19") (pinfunction "Y2_19") (pintype "passive"))
      (node (ref "U1") (pin "21") (pinfunction "XTAL_32K_P_21") (pintype "passive"))
    )
    (net (code "18") (name "/IO16{slash}DVP_Y5") (class "Default")
      (node (ref "CN1") (pin "20") (pinfunction "Y5_20") (pintype "passive"))
      (node (ref "U1") (pin "22") (pinfunction "XTAL_32K_N_22") (pintype "passive"))
    )
    (net (code "19") (name "/IO17{slash}DVP_Y3") (class "Default")
      (node (ref "CN1") (pin "21") (pinfunction "Y3_21") (pintype "passive"))
      (node (ref "U1") (pin "23") (pinfunction "GPIO17_23") (pintype "passive"))
    )
    (net (code "20") (name "/IO18{slash}DVP_Y4") (class "Default")
      (node (ref "CN1") (pin "22") (pinfunction "Y4_22") (pintype "passive"))
      (node (ref "U1") (pin "24") (pinfunction "GPIO18_24") (pintype "passive"))
    )
    (net (code "21") (name "/IO21{slash}BTN1") (class "Default")
      (node (ref "C21") (pin "2") (pinfunction "2_2") (pintype "passive"))
      (node (ref "R13") (pin "1") (pinfunction "1_1") (pintype "passive"))
      (node (ref "SW3") (pin "3") (pinfunction "3_3") (pintype "passive"))
      (node (ref "SW3") (pin "4") (pinfunction "4_4") (pintype "passive"))
      (node (ref "U1") (pin "27") (pinfunction "GPIO21_27") (pintype "passive"))
    )
    (net (code "22") (name "/IO33{slash}CAM_PWR") (class "Default")
      (node (ref "R2") (pin "1") (pinfunction "1_1") (pintype "passive"))
      (node (ref "U1") (pin "38") (pinfunction "GPIO33_38") (pintype "passive"))
    )
    (net (code "23") (name "/IO37{slash}BTN2") (class "Default")
      (node (ref "C24") (pin "2") (pinfunction "2_2") (pintype "passive"))
      (node (ref "R14") (pin "1") (pinfunction "1_1") (pintype "passive"))
      (node (ref "SW4") (pin "3") (pinfunction "3_3") (pintype "passive"))
      (node (ref "SW4") (pin "4") (pinfunction "4_4") (pintype "passive"))
      (node (ref "U1") (pin "42") (pinfunction "GPIO37_42") (pintype "passive"))
    )
    (net (code "24") (name "/IO38{slash}DVP_VSYNC") (class "Default")
      (node (ref "CN1") (pin "7") (pinfunction "VSYNC_7") (pintype "passive"))
      (node (ref "U1") (pin "43") (pinfunction "GPIO38_43") (pintype "passive"))
    )
    (net (code "25") (name "/IO39{slash}CAM_SCL") (class "Default")
      (node (ref "CN1") (pin "5") (pinfunction "SCL_5") (pintype "passive"))
      (node (ref "R22") (pin "2") (pinfunction "2_2") (pintype "passive"))
      (node (ref "U1") (pin "44") (pinfunction "MTCK_44") (pintype "passive"))
    )
    (net (code "26") (name "/IO40{slash}CAM_SDA") (class "Default")
      (node (ref "CN1") (pin "3") (pinfunction "SDA_3") (pintype "passive"))
      (node (ref "R21") (pin "2") (pinfunction "2_2") (pintype "passive"))
      (node (ref "U1") (pin "45") (pinfunction "MTDO_45") (pintype "passive"))
    )
    (net (code "27") (name "/IO45{slash}LED_Status") (class "Default")
      (node (ref "R19") (pin "2") (pinfunction "2_2") (pintype "passive"))
      (node (ref "U1") (pin "51") (pinfunction "GPIO45_51") (pintype "passive"))
    )
    (net (code "28") (name "/IO46{slash}LED_Ctrl") (class "Default")
      (node (ref "U1") (pin "52") (pinfunction "GPIO46_52") (pintype "passive"))
      (node (ref "U7") (pin "1") (pinfunction "1_1") (pintype "passive"))
    )
    (net (code "29") (name "/IO47{slash}DVP_HREF") (class "Default")
      (node (ref "CN1") (pin "9") (pinfunction "HREF_9") (pintype "passive"))
      (node (ref "U1") (pin "37") (pinfunction "SPICLK_P_37") (pintype "passive"))
    )
    (net (code "30") (name "/IO48{slash}DVP_Y9") (class "Default")
      (node (ref "CN1") (pin "12") (pinfunction "Y9_12") (pintype "passive"))
      (node (ref "U1") (pin "36") (pinfunction "SPICLK_N_36") (pintype "passive"))
    )
    (net (code "31") (name "/LNA") (class "Default")
      (node (ref "C3") (pin "2") (pinfunction "2_2") (pintype "passive"))
      (node (ref "L1") (pin "1") (pinfunction "1_1") (pintype "passive"))
      (node (ref "U1") (pin "1") (pinfunction "LNA_IN_1") (pintype "passive"))
    )
    (net (code "32") (name "/SPICLK") (class "Default")
      (node (ref "U1") (pin "33") (pinfunction "SPICLK_33") (pintype "passive"))
      (node (ref "U5") (pin "6") (pinfunction "CLK_6") (pintype "passive"))
    )
    (net (code "33") (name "/SPICS0") (class "Default")
      (node (ref "U1") (pin "32") (pinfunction "SPICS0_32") (pintype "passive"))
      (node (ref "U5") (pin "1") (pinfunction "/CS_1") (pintype "passive"))
    )
    (net (code "34") (name "/SPID") (class "Default")
      (node (ref "U1") (pin "35") (pinfunction "SPID_35") (pintype "passive"))
      (node (ref "U5") (pin "5") (pinfunction "DI_5") (pintype "passive"))
    )
    (net (code "35") (name "/SPIHD") (class "Default")
      (node (ref "U1") (pin "30") (pinfunction "SPIHD_30") (pintype "passive"))
      (node (ref "U5") (pin "7") (pinfunction "/HOLD_7") (pintype "passive"))
    )
    (net (code "36") (name "/SPIQ") (class "Default")
      (node (ref "U1") (pin "34") (pinfunction "SPIQ_34") (pintype "passive"))
      (node (ref "U5") (pin "2") (pinfunction "DO_2") (pintype "passive"))
    )
    (net (code "37") (name "/SPIWP") (class "Default")
      (node (ref "U1") (pin "31") (pinfunction "SPIWP_31") (pintype "passive"))
      (node (ref "U5") (pin "3") (pinfunction "/WP_3") (pintype "passive"))
    )
    (net (code "38") (name "/VDD_SPI") (class "Default")
      (node (ref "C11") (pin "2") (pinfunction "2_2") (pintype "passive"))
      (node (ref "C13") (pin "2") (pinfunction "2_2") (pintype "passive"))
      (node (ref "U1") (pin "29") (pinfunction "VDD_SPI_29") (pintype "passive"))
      (node (ref "U5") (pin "8") (pinfunction "VDD_8") (pintype "passive"))
    )
    (net (code "39") (name "/XTAL_N") (class "Default")
      (node (ref "C26") (pin "2") (pinfunction "2_2") (pintype "passive"))
      (node (ref "U1") (pin "53") (pinfunction "XTAL_N_53") (pintype "passive"))
      (node (ref "Y1") (pin "3") (pinfunction "X2_3") (pintype "passive"))
    )
    (net (code "40") (name "/XTAL_P") (class "Default")
      (node (ref "L3") (pin "1") (pinfunction "1_1") (pintype "passive"))
      (node (ref "U1") (pin "54") (pinfunction "XTAL_P_54") (pintype "passive"))
    )
    (net (code "41") (name "1.8V") (class "Default")
      (node (ref "C37") (pin "2") (pinfunction "2_2") (pintype "passive"))
      (node (ref "CN1") (pin "10") (pinfunction "DVDD_10") (pintype "passive"))
      (node (ref "U9") (pin "5") (pinfunction "VOUT_5") (pintype "passive"))
    )
    (net (code "42") (name "2.8V") (class "Default")
      (node (ref "C36") (pin "2") (pinfunction "2_2") (pintype "passive"))
      (node (ref "CN1") (pin "11") (pinfunction "DOVDD_11") (pintype "passive"))
      (node (ref "D6") (pin "2") (pinfunction "2_2") (pintype "passive"))
      (node (ref "FB1") (pin "1") (pinfunction "1_1") (pintype "passive"))
      (node (ref "J3") (pin "2") (pinfunction "2_2") (pintype "passive"))
      (node (ref "R21") (pin "1") (pinfunction "1_1") (pintype "passive"))
      (node (ref "R22") (pin "1") (pinfunction "1_1") (pintype "passive"))
      (node (ref "R6") (pin "2") (pinfunction "2_2") (pintype "passive"))
      (node (ref "R7") (pin "2") (pinfunction "2_2") (pintype "passive"))
      (node (ref "U10") (pin "5") (pinfunction "VOUT_5") (pintype "passive"))
    )
    (net (code "43") (name "3V3") (class "Default")
      (node (ref "C10") (pin "2") (pinfunction "2_2") (pintype "passive"))
      (node (ref "C14") (pin "2") (pinfunction "2_2") (pintype "passive"))
      (node (ref "C16") (pin "2") (pinfunction "2_2") (pintype "passive"))
      (node (ref "C18") (pin "2") (pinfunction "2_2") (pintype "passive"))
      (node (ref "C19") (pin "2") (pinfunction "2_2") (pintype "passive"))
      (node (ref "C23") (pin "2") (pinfunction "2_2") (pintype "passive"))
      (node (ref "C28") (pin "2") (pinfunction "2_2") (pintype "passive"))
      (node (ref "C31") (pin "2") (pinfunction "2_2") (pintype "passive"))
      (node (ref "C33") (pin "2") (pinfunction "2_2") (pintype "passive"))
      (node (ref "C8") (pin "2") (pinfunction "2_2") (pintype "passive"))
      (node (ref "J3") (pin "1") (pinfunction "1_1") (pintype "passive"))
      (node (ref "L2") (pin "1") (pinfunction "1_1") (pintype "passive"))
      (node (ref "L4") (pin "2") (pinfunction "2_2") (pintype "passive"))
      (node (ref "R1") (pin "1") (pinfunction "1_1") (pintype "passive"))
      (node (ref "R10") (pin "2") (pinfunction "2_2") (pintype "passive"))
      (node (ref "R11") (pin "2") (pinfunction "2_2") (pintype "passive"))
      (node (ref "R13") (pin "2") (pinfunction "2_2") (pintype "passive"))
      (node (ref "R14") (pin "2") (pinfunction "2_2") (pintype "passive"))
      (node (ref "R23") (pin "1") (pinfunction "1_1") (pintype "passive"))
      (node (ref "U1") (pin "20") (pinfunction "VDD3P3_RTC_20") (pintype "passive"))
      (node (ref "U1") (pin "46") (pinfunction "VDD3P3_CPU_46") (pintype "passive"))
      (node (ref "U1") (pin "55") (pinfunction "VDDA_55") (pintype "passive"))
      (node (ref "U1") (pin "56") (pinfunction "VDDA_56") (pintype "passive"))
      (node (ref "U6") (pin "6") (pinfunction "VOS_6") (pintype "power_in"))
      (node (ref "U8") (pin "3") (pinfunction "3_3") (pintype "passive"))
    )
    (net (code "44") (name "AVCC_2.8V") (class "Default")
      (node (ref "C32") (pin "2") (pinfunction "2_2") (pintype "passive"))
      (node (ref "CN1") (pin "4") (pinfunction "AVDD_4") (pintype "passive"))
      (node (ref "FB1") (pin "2") (pinfunction "2_2") (pintype "passive"))
    )
    (net (code "45") (name "GND") (class "Default")
      (node (ref "C1") (pin "1") (pinfunction "1_1") (pintype "passive"))
      (node (ref "C10") (pin "1") (pinfunction "1_1") (pintype "passive"))
      (node (ref "C11") (pin "1") (pinfunction "1_1") (pintype "passive"))
      (node (ref "C12") (pin "1") (pinfunction "1_1") (pintype "passive"))
      (node (ref "C13") (pin "1") (pinfunction "1_1") (pintype "passive"))
      (node (ref "C14") (pin "1") (pinfunction "1_1") (pintype "passive"))
      (node (ref "C15") (pin "1") (pinfunction "1_1") (pintype "passive"))
      (node (ref "C16") (pin "1") (pinfunction "1_1") (pintype "passive"))
      (node (ref "C17") (pin "1") (pinfunction "1_1") (pintype "passive"))
      (node (ref "C18") (pin "1") (pinfunction "1_1") (pintype "passive"))
      (node (ref "C19") (pin "1") (pinfunction "1_1") (pintype "passive"))
      (node (ref "C2") (pin "1") (pinfunction "1_1") (pintype "passive"))
      (node (ref "C20") (pin "1") (pinfunction "1_1") (pintype "passive"))
      (node (ref "C21") (pin "1") (pinfunction "1_1") (pintype "passive"))
      (node (ref "C22") (pin "2") (pinfunction "2_2") (pintype "passive"))
      (node (ref "C23") (pin "1") (pinfunction "1_1") (pintype "passive"))
      (node (ref "C24") (pin "1") (pinfunction "1_1") (pintype "passive"))
      (node (ref "C25") (pin "1") (pinfunction "1_1") (pintype "passive"))
      (node (ref "C26") (pin "1") (pinfunction "1_1") (pintype "passive"))
      (node (ref "C27") (pin "1") (pinfunction "1_1") (pintype "passive"))
      (node (ref "C28") (pin "1") (pinfunction "1_1") (pintype "passive"))
      (node (ref "C29") (pin "1") (pinfunction "1_1") (pintype "passive"))
      (node (ref "C3") (pin "1") (pinfunction "1_1") (pintype "passive"))
      (node (ref "C30") (pin "1") (pinfunction "1_1") (pintype "passive"))
      (node (ref "C31") (pin "1") (pinfunction "1_1") (pintype "passive"))
      (node (ref "C32") (pin "1") (pinfunction "1_1") (pintype "passive"))
      (node (ref "C33") (pin "1") (pinfunction "1_1") (pintype "passive"))
      (node (ref "C34") (pin "1") (pinfunction "1_1") (pintype "passive"))
      (node (ref "C35") (pin "1") (pinfunction "1_1") (pintype "passive"))
      (node (ref "C36") (pin "1") (pinfunction "1_1") (pintype "passive"))
      (node (ref "C37") (pin "1") (pinfunction "1_1") (pintype "passive"))
      (node (ref "C4") (pin "1") (pinfunction "1_1") (pintype "passive"))
      (node (ref "C7") (pin "1") (pinfunction "1_1") (pintype "passive"))
      (node (ref "C8") (pin "1") (pinfunction "1_1") (pintype "passive"))
      (node (ref "C9") (pin "1") (pinfunction "1_1") (pintype "passive"))
      (node (ref "CN1") (pin "15") (pinfunction "DGND_15") (pintype "passive"))
      (node (ref "CN1") (pin "2") (pinfunction "AGND_2") (pintype "passive"))
      (node (ref "CN1") (pin "23") (pinfunction "NC_23") (pintype "passive"))
      (node (ref "CN1") (pin "25") (pinfunction "GND_25") (pintype "passive"))
      (node (ref "CN1") (pin "26") (pinfunction "GND_26") (pintype "passive"))
      (node (ref "D2") (pin "2") (pinfunction "GND_2") (pintype "power_in"))
      (node (ref "D7") (pin "1") (pinfunction "1_1") (pintype "passive"))
      (node (ref "D8") (pin "1") (pinfunction "1_1") (pintype "passive"))
      (node (ref "J1") (pin "A1B12") (pinfunction "GND_A1B12_A1B12") (pintype "passive"))
      (node (ref "J1") (pin "B1A12") (pinfunction "GND_B1A12_B1A12") (pintype "passive"))
      (node (ref "J1") (pin "S1") (pinfunction "SHEILD_1_S1") (pintype "passive"))
      (node (ref "J1") (pin "S2") (pinfunction "SHEILD_2_S2") (pintype "passive"))
      (node (ref "J1") (pin "S3") (pinfunction "SHEILD_3_S3") (pintype "passive"))
      (node (ref "J1") (pin "S4") (pinfunction "SHEILD_4_S4") (pintype "passive"))
      (node (ref "J2") (pin "G1") (pinfunction "GND_G1") (pintype "passive"))
      (node (ref "J2") (pin "G2") (pinfunction "GND_G2") (pintype "passive"))
      (node (ref "J3") (pin "6") (pinfunction "6_6") (pintype "passive"))
      (node (ref "P1") (pin "2") (pinfunction "2_2") (pintype "passive"))
      (node (ref "R12") (pin "1") (pinfunction "1_1") (pintype "passive"))
      (node (ref "R15") (pin "1") (pinfunction "1_1") (pintype "passive"))
      (node (ref "R20") (pin "1") (pinfunction "1_1") (pintype "passive"))
      (node (ref "R3") (pin "1") (pinfunction "1_1") (pintype "passive"))
      (node (ref "R4") (pin "2") (pinfunction "2_2") (pintype "passive"))
      (node (ref "R5") (pin "2") (pinfunction "2_2") (pintype "passive"))
      (node (ref "SW1") (pin "1") (pinfunction "1_1") (pintype "passive"))
      (node (ref "SW1") (pin "2") (pinfunction "2_2") (pintype "passive"))
      (node (ref "SW2") (pin "1") (pinfunction "1_1") (pintype "passive"))
      (node (ref "SW2") (pin "2") (pinfunction "2_2") (pintype "passive"))
      (node (ref "SW3") (pin "1") (pinfunction "1_1") (pintype "passive"))
      (node (ref "SW3") (pin "2") (pinfunction "2_2") (pintype "passive"))
      (node (ref "SW4") (pin "1") (pinfunction "1_1") (pintype "passive"))
      (node (ref "SW4") (pin "2") (pinfunction "2_2") (pintype "passive"))
      (node (ref "U1") (pin "57") (pinfunction "GND_57") (pintype "passive"))
      (node (ref "U10") (pin "2") (pinfunction "GND_2") (pintype "power_in"))
      (node (ref "U4") (pin "2") (pinfunction "VSS_2") (pintype "power_in"))
      (node (ref "U5") (pin "4") (pinfunction "GND_4") (pintype "passive"))
      (node (ref "U6") (pin "1") (pinfunction "GND_1") (pintype "passive"))
      (node (ref "U7") (pin "2") (pinfunction "2_2") (pintype "passive"))
      (node (ref "U9") (pin "2") (pinfunction "GND_2") (pintype "power_in"))
      (node (ref "Y1") (pin "2") (pinfunction "GND_2") (pintype "passive"))
      (node (ref "Y1") (pin "4") (pinfunction "GND_4") (pintype "passive"))
    )
    (net (code "46") (name "Net-(C4-Pad2)") (class "Default")
      (node (ref "C4") (pin "2") (pinfunction "2_2") (pintype "passive"))
      (node (ref "J2") (pin "SIG") (pinfunction "SIG_SIG") (pintype "passive"))
      (node (ref "L1") (pin "2") (pinfunction "2_2") (pintype "passive"))
    )
    (net (code "47") (name "Net-(C12-Pad2)") (class "Default")
      (node (ref "C12") (pin "2") (pinfunction "2_2") (pintype "passive"))
      (node (ref "C15") (pin "2") (pinfunction "2_2") (pintype "passive"))
      (node (ref "L2") (pin "2") (pinfunction "2_2") (pintype "passive"))
      (node (ref "U1") (pin "2") (pinfunction "VDD3P3_2") (pintype "passive"))
      (node (ref "U1") (pin "3") (pinfunction "VDD3P3_3") (pintype "passive"))
    )
    (net (code "48") (name "Net-(C27-Pad2)") (class "Default")
      (node (ref "C27") (pin "2") (pinfunction "2_2") (pintype "passive"))
      (node (ref "C29") (pin "2") (pinfunction "2_2") (pintype "passive"))
      (node (ref "CN1") (pin "24") (pinfunction "NC_24") (pintype "passive"))
      (node (ref "D6") (pin "1") (pinfunction "1_1") (pintype "passive"))
    )
    (net (code "49") (name "Net-(CN1-PWDN)") (class "Default")
      (node (ref "CN1") (pin "8") (pinfunction "PWDN_8") (pintype "passive"))
      (node (ref "R20") (pin "2") (pinfunction "2_2") (pintype "passive"))
    )
    (net (code "50") (name "Net-(CN1-RESET)") (class "Default")
      (node (ref "C30") (pin "2") (pinfunction "2_2") (pintype "passive"))
      (node (ref "CN1") (pin "6") (pinfunction "RESET_6") (pintype "passive"))
      (node (ref "R23") (pin "2") (pinfunction "2_2") (pintype "passive"))
    )
    (net (code "51") (name "Net-(D3-Pad2)") (class "Default")
      (node (ref "D3") (pin "2") (pinfunction "2_2") (pintype "passive"))
      (node (ref "R9") (pin "1") (pinfunction "1_1") (pintype "passive"))
    )
    (net (code "52") (name "Net-(D7-Pad2)") (class "Default")
      (node (ref "D7") (pin "2") (pinfunction "2_2") (pintype "passive"))
      (node (ref "R18") (pin "1") (pinfunction "1_1") (pintype "passive"))
    )
    (net (code "53") (name "Net-(D8-Pad2)") (class "Default")
      (node (ref "D8") (pin "2") (pinfunction "2_2") (pintype "passive"))
      (node (ref "R19") (pin "1") (pinfunction "1_1") (pintype "passive"))
    )
    (net (code "54") (name "Net-(J1-CC1)") (class "Default")
      (node (ref "J1") (pin "A5") (pinfunction "CC1_A5") (pintype "passive"))
      (node (ref "R4") (pin "1") (pinfunction "1_1") (pintype "passive"))
    )
    (net (code "55") (name "Net-(J1-CC2)") (class "Default")
      (node (ref "J1") (pin "B5") (pinfunction "CC2_B5") (pintype "passive"))
      (node (ref "R5") (pin "1") (pinfunction "1_1") (pintype "passive"))
    )
    (net (code "56") (name "Net-(R1-Pad2)") (class "Default")
      (node (ref "R1") (pin "2") (pinfunction "2_2") (pintype "passive"))
      (node (ref "R2") (pin "2") (pinfunction "2_2") (pintype "passive"))
      (node (ref "U8") (pin "1") (pinfunction "1_1") (pintype "passive"))
    )
    (net (code "57") (name "Net-(U4-PROG)") (class "Default")
      (node (ref "R12") (pin "2") (pinfunction "2_2") (pintype "passive"))
      (node (ref "U4") (pin "5") (pinfunction "PROG_5") (pintype "passive"))
    )
    (net (code "58") (name "Net-(U4-STAT)") (class "Default")
      (node (ref "D3") (pin "1") (pinfunction "1_1") (pintype "passive"))
      (node (ref "U4") (pin "1") (pinfunction "STAT_1") (pintype "passive"))
    )
    (net (code "59") (name "Net-(U6-MODE)") (class "Default")
      (node (ref "R15") (pin "2") (pinfunction "2_2") (pintype "passive"))
      (node (ref "U6") (pin "3") (pinfunction "MODE_3") (pintype "power_in"))
    )
    (net (code "60") (name "Net-(U6-SW)") (class "Default")
      (node (ref "L4") (pin "1") (pinfunction "1_1") (pintype "passive"))
      (node (ref "U6") (pin "5") (pinfunction "SW_5") (pintype "power_in"))
    )
    (net (code "61") (name "Net-(U9-EN)") (class "Default")
      (node (ref "R24") (pin "2") (pinfunction "2_2") (pintype "passive"))
      (node (ref "U9") (pin "3") (pinfunction "EN_3") (pintype "passive"))
    )
    (net (code "62") (name "Net-(U10-EN)") (class "Default")
      (node (ref "R25") (pin "2") (pinfunction "2_2") (pintype "passive"))
      (node (ref "U10") (pin "3") (pinfunction "EN_3") (pintype "passive"))
    )
    (net (code "63") (name "Net-(U10-VIN)") (class "Default")
      (node (ref "C34") (pin "2") (pinfunction "2_2") (pintype "passive"))
      (node (ref "C35") (pin "2") (pinfunction "2_2") (pintype "passive"))
      (node (ref "R24") (pin "1") (pinfunction "1_1") (pintype "passive"))
      (node (ref "R25") (pin "1") (pinfunction "1_1") (pintype "passive"))
      (node (ref "U10") (pin "1") (pinfunction "VIN_1") (pintype "power_in"))
      (node (ref "U8") (pin "2") (pinfunction "2_2") (pintype "passive"))
      (node (ref "U9") (pin "1") (pinfunction "VIN_1") (pintype "power_in"))
    )
    (net (code "64") (name "Net-(Y1-X1)") (class "Default")
      (node (ref "C22") (pin "1") (pinfunction "1_1") (pintype "passive"))
      (node (ref "L3") (pin "2") (pinfunction "2_2") (pintype "passive"))
      (node (ref "Y1") (pin "1") (pinfunction "X1_1") (pintype "passive"))
    )
    (net (code "65") (name "TYPE-C_5V") (class "Default")
      (node (ref "C1") (pin "2") (pinfunction "2_2") (pintype "passive"))
      (node (ref "C2") (pin "2") (pinfunction "2_2") (pintype "passive"))
      (node (ref "C7") (pin "2") (pinfunction "2_2") (pintype "passive"))
      (node (ref "D1") (pin "2") (pinfunction "2_2") (pintype "passive"))
      (node (ref "D2") (pin "5") (pinfunction "VBUS_5") (pintype "power_in"))
      (node (ref "J1") (pin "A4B9") (pinfunction "VBUS_A4B9_A4B9") (pintype "passive"))
      (node (ref "J1") (pin "B4A9") (pinfunction "VBUS_B4A9_B4A9") (pintype "passive"))
      (node (ref "R18") (pin "2") (pinfunction "2_2") (pintype "passive"))
      (node (ref "R3") (pin "2") (pinfunction "2_2") (pintype "passive"))
      (node (ref "R9") (pin "2") (pinfunction "2_2") (pintype "passive"))
      (node (ref "U2") (pin "1") (pinfunction "1_1") (pintype "passive"))
      (node (ref "U4") (pin "4") (pinfunction "VDD_4") (pintype "power_in"))
    )
    (net (code "66") (name "VBAT") (class "Default")
      (node (ref "C20") (pin "2") (pinfunction "2_2") (pintype "passive"))
      (node (ref "P1") (pin "1") (pinfunction "1_1") (pintype "passive"))
      (node (ref "U2") (pin "3") (pinfunction "3_3") (pintype "passive"))
      (node (ref "U4") (pin "3") (pinfunction "VBAT_3") (pintype "power_in"))
    )
    (net (code "67") (name "VIN") (class "Default")
      (node (ref "C25") (pin "2") (pinfunction "2_2") (pintype "passive"))
      (node (ref "D1") (pin "1") (pinfunction "1_1") (pintype "passive"))
      (node (ref "U2") (pin "2") (pinfunction "2_2") (pintype "passive"))
      (node (ref "U6") (pin "2") (pinfunction "VIN_2") (pintype "passive"))
      (node (ref "U6") (pin "4") (pinfunction "EN_4") (pintype "passive"))
    )
    (net (code "68") (name "unconnected-(CN1-NC-Pad1)") (class "Default")
      (node (ref "CN1") (pin "1") (pinfunction "NC_1") (pintype "passive+no_connect"))
    )
    (net (code "69") (name "unconnected-(J1-SBU1-PadA8)") (class "Default")
      (node (ref "J1") (pin "A8") (pinfunction "SBU1_A8") (pintype "passive+no_connect"))
    )
    (net (code "70") (name "unconnected-(J1-SBU2-PadB8)") (class "Default")
      (node (ref "J1") (pin "B8") (pinfunction "SBU2_B8") (pintype "passive+no_connect"))
    )
    (net (code "71") (name "unconnected-(P1-SHIELD-PadS1)") (class "Default")
      (node (ref "P1") (pin "S1") (pinfunction "SHIELD_S1") (pintype "passive+no_connect"))
    )
    (net (code "72") (name "unconnected-(P1-SHIELD-PadS2)") (class "Default")
      (node (ref "P1") (pin "S2") (pinfunction "SHIELD_S2") (pintype "passive+no_connect"))
    )
    (net (code "73") (name "unconnected-(U1-GPIO1-Pad6)") (class "Default")
      (node (ref "U1") (pin "6") (pinfunction "GPIO1_6") (pintype "passive+no_connect"))
    )
    (net (code "74") (name "unconnected-(U1-GPIO2-Pad7)") (class "Default")
      (node (ref "U1") (pin "7") (pinfunction "GPIO2_7") (pintype "passive+no_connect"))
    )
    (net (code "75") (name "unconnected-(U1-GPIO3-Pad8)") (class "Default")
      (node (ref "U1") (pin "8") (pinfunction "GPIO3_8") (pintype "passive+no_connect"))
    )
    (net (code "76") (name "unconnected-(U1-GPIO6-Pad11)") (class "Default")
      (node (ref "U1") (pin "11") (pinfunction "GPIO6_11") (pintype "passive"))
    )
    (net (code "77") (name "unconnected-(U1-GPIO7-Pad12)") (class "Default")
      (node (ref "U1") (pin "12") (pinfunction "GPIO7_12") (pintype "passive"))
    )
    (net (code "78") (name "unconnected-(U1-GPIO8-Pad13)") (class "Default")
      (node (ref "U1") (pin "13") (pinfunction "GPIO8_13") (pintype "passive"))
    )
    (net (code "79") (name "unconnected-(U1-GPIO9-Pad14)") (class "Default")
      (node (ref "U1") (pin "14") (pinfunction "GPIO9_14") (pintype "passive"))
    )
    (net (code "80") (name "unconnected-(U1-GPIO34-Pad39)") (class "Default")
      (node (ref "U1") (pin "39") (pinfunction "GPIO34_39") (pintype "passive+no_connect"))
    )
    (net (code "81") (name "unconnected-(U1-GPIO35-Pad40)") (class "Default")
      (node (ref "U1") (pin "40") (pinfunction "GPIO35_40") (pintype "passive+no_connect"))
    )
    (net (code "82") (name "unconnected-(U1-GPIO36-Pad41)") (class "Default")
      (node (ref "U1") (pin "41") (pinfunction "GPIO36_41") (pintype "passive+no_connect"))
    )
    (net (code "83") (name "unconnected-(U1-MTDI-Pad47)") (class "Default")
      (node (ref "U1") (pin "47") (pinfunction "MTDI_47") (pintype "passive"))
    )
    (net (code "84") (name "unconnected-(U1-MTMS-Pad48)") (class "Default")
      (node (ref "U1") (pin "48") (pinfunction "MTMS_48") (pintype "passive"))
    )
    (net (code "85") (name "unconnected-(U1-SPICS1-Pad28)") (class "Default")
      (node (ref "U1") (pin "28") (pinfunction "SPICS1_28") (pintype "passive+no_connect"))
    )
    (net (code "86") (name "unconnected-(U1-U0RXD-Pad50)") (class "Default")
      (node (ref "U1") (pin "50") (pinfunction "U0RXD_50") (pintype "passive"))
    )
    (net (code "87") (name "unconnected-(U1-U0TXD-Pad49)") (class "Default")
      (node (ref "U1") (pin "49") (pinfunction "U0TXD_49") (pintype "passive"))
    )
    (net (code "88") (name "unconnected-(U9-NC-Pad4)") (class "Default")
      (node (ref "U9") (pin "4") (pinfunction "NC_4") (pintype "passive+no_connect"))
    )
    (net (code "89") (name "unconnected-(U10-NC-Pad4)") (class "Default")
      (node (ref "U10") (pin "4") (pinfunction "NC_4") (pintype "passive+no_connect"))
    )
  )
)
